# enclosure_controller_esp32.net
KiCad netlist of a schematic drawn in EAGLE
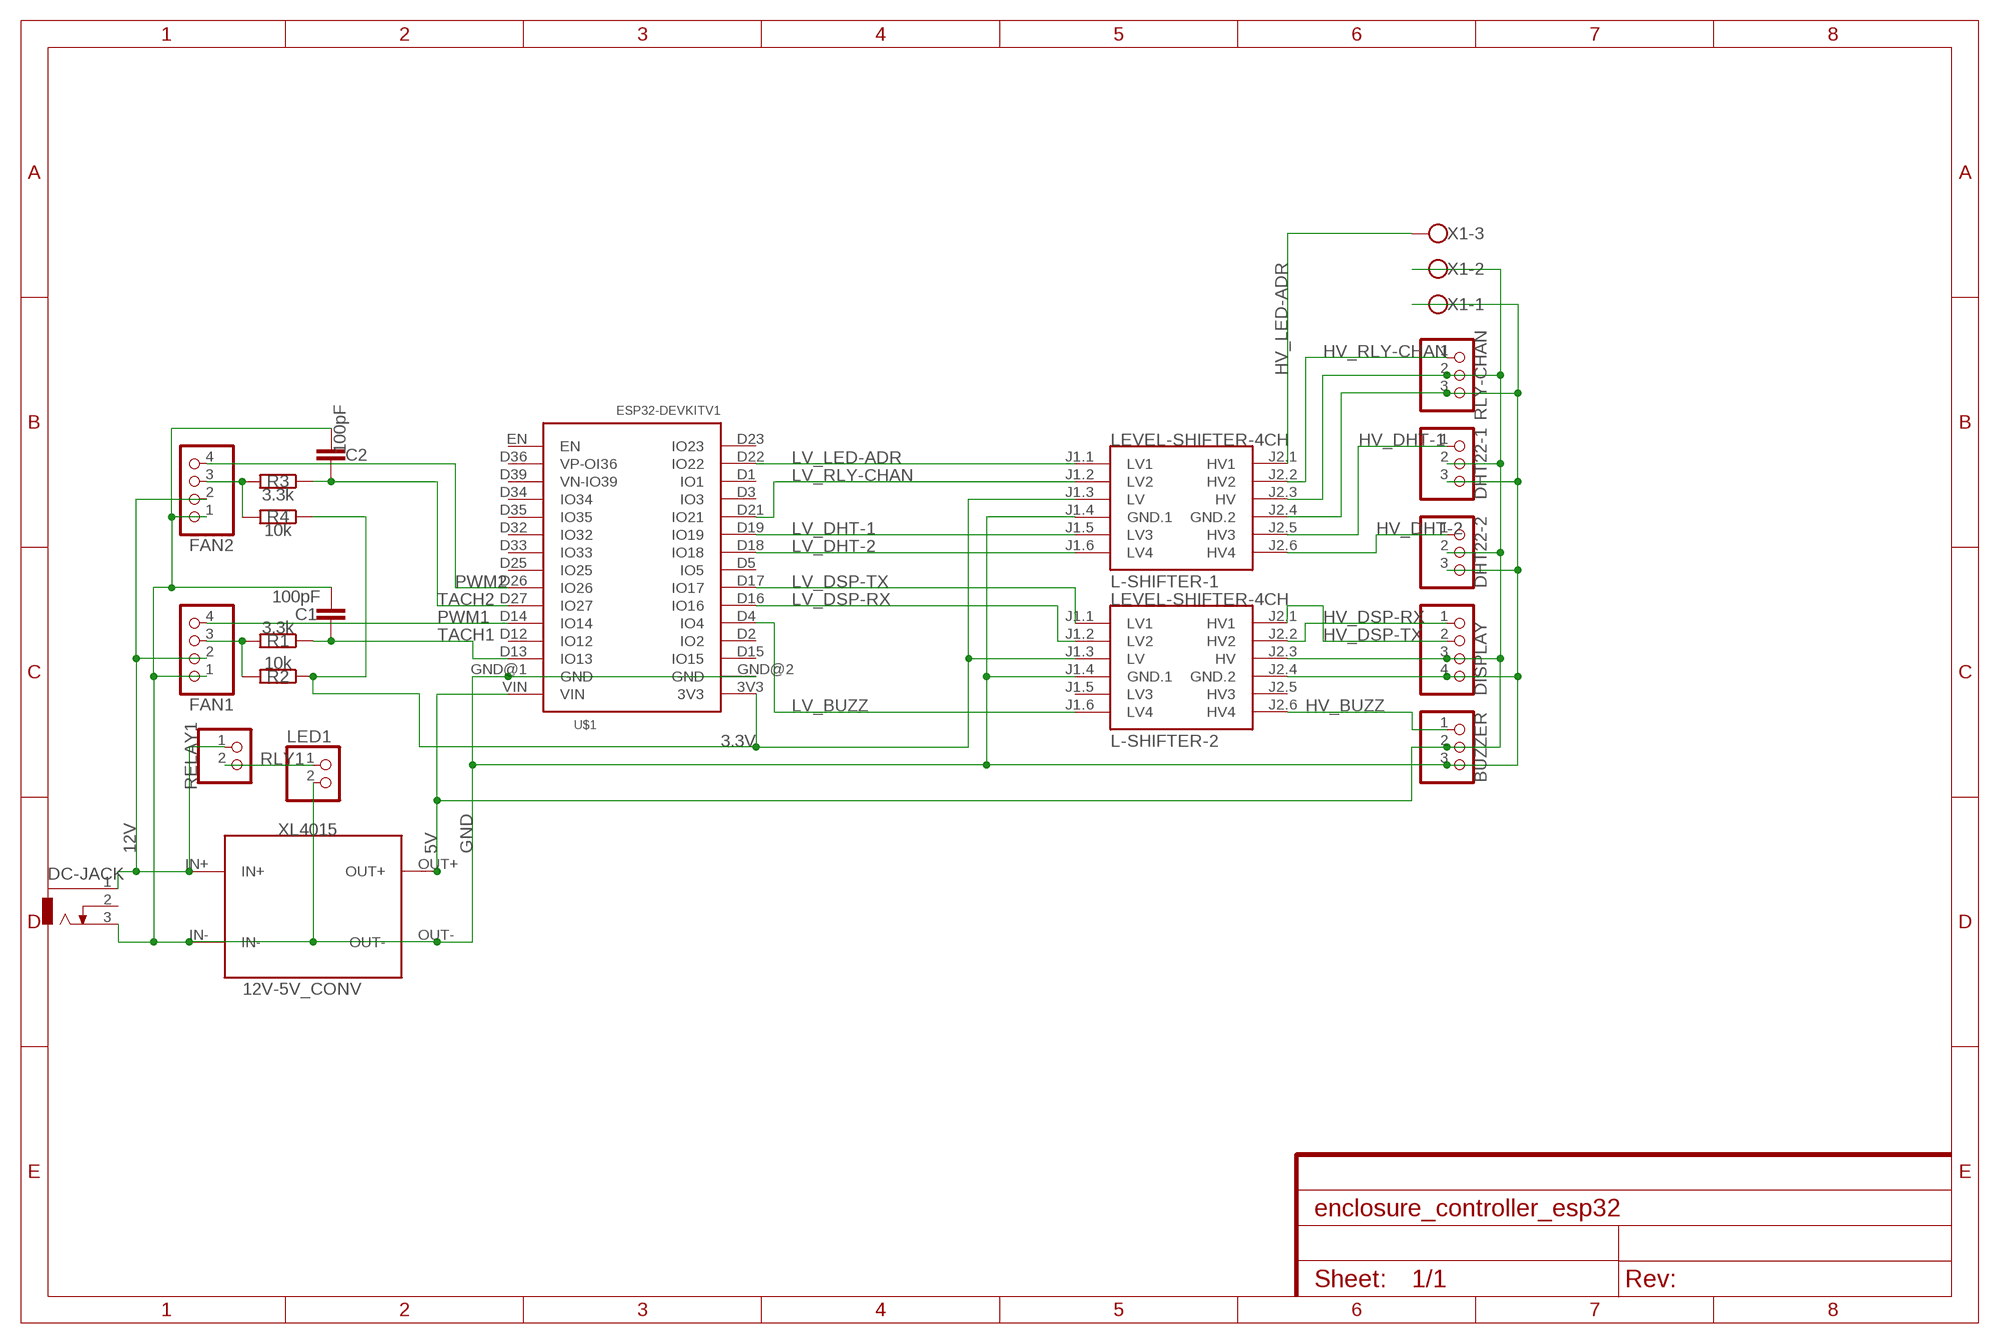
[diagram p0: schematic, sheet 1]

(export (version "E")
  (design (tool "Eeschema 10.0.6"))
  (components
    (comp (ref "12V-5V_CONV")
      (value "XL4015")
      (footprint "eagle-import:XL4015")
      (libsource (lib "eagle-import") (part "XL4015"))
    )
    (comp (ref "BUZZER")
      (value "PINHD-1X3")
      (footprint "eagle-import:1X03")
      (libsource (lib "eagle-import") (part "PINHD-1X3"))
    )
    (comp (ref "C1")
      (value "100pF")
      (footprint "eagle-import:C050-025X075")
      (libsource (lib "eagle-import") (part "C-EU050-025X075"))
    )
    (comp (ref "C2")
      (value "100pF")
      (footprint "eagle-import:C050-025X075")
      (libsource (lib "eagle-import") (part "C-EU050-025X075"))
    )
    (comp (ref "DC-JACK")
      (value "DCJ0303")
      (footprint "eagle-import:DCJ0303")
      (libsource (lib "eagle-import") (part "DCJ0303"))
    )
    (comp (ref "DHT22-1")
      (value "PINHD-1X3")
      (footprint "eagle-import:1X03")
      (libsource (lib "eagle-import") (part "PINHD-1X3"))
    )
    (comp (ref "DHT22-2")
      (value "PINHD-1X3")
      (footprint "eagle-import:1X03")
      (libsource (lib "eagle-import") (part "PINHD-1X3"))
    )
    (comp (ref "DISPLAY")
      (value "PINHD-1X4")
      (footprint "eagle-import:1X04")
      (libsource (lib "eagle-import") (part "PINHD-1X4"))
    )
    (comp (ref "FAN1")
      (value "PINHD-1X4")
      (footprint "eagle-import:1X04")
      (libsource (lib "eagle-import") (part "PINHD-1X4"))
    )
    (comp (ref "FAN2")
      (value "PINHD-1X4")
      (footprint "eagle-import:1X04")
      (libsource (lib "eagle-import") (part "PINHD-1X4"))
    )
    (comp (ref "L-SHIFTER-1")
      (value "LEVEL-SHIFTER-4CH")
      (footprint "eagle-import:LEVEL-SHIFTER-4CH")
      (libsource (lib "eagle-import") (part "LEVEL-SHIFTER-4CH"))
    )
    (comp (ref "L-SHIFTER-2")
      (value "LEVEL-SHIFTER-4CH")
      (footprint "eagle-import:LEVEL-SHIFTER-4CH")
      (libsource (lib "eagle-import") (part "LEVEL-SHIFTER-4CH"))
    )
    (comp (ref "LED1")
      (value "PINHD-1X2")
      (footprint "eagle-import:1X02")
      (libsource (lib "eagle-import") (part "PINHD-1X2"))
    )
    (comp (ref "R1")
      (value "3.3k")
      (footprint "eagle-import:0207_10")
      (libsource (lib "eagle-import") (part "R-EU_0207/10"))
    )
    (comp (ref "R2")
      (value "10k")
      (footprint "eagle-import:0207_10")
      (libsource (lib "eagle-import") (part "R-EU_0207/10"))
    )
    (comp (ref "R3")
      (value "3.3k")
      (footprint "eagle-import:0207_10")
      (libsource (lib "eagle-import") (part "R-EU_0207/10"))
    )
    (comp (ref "R4")
      (value "10k")
      (footprint "eagle-import:0207_10")
      (libsource (lib "eagle-import") (part "R-EU_0207/10"))
    )
    (comp (ref "RELAY1")
      (value "PINHD-1X2")
      (footprint "eagle-import:1X02")
      (libsource (lib "eagle-import") (part "PINHD-1X2"))
    )
    (comp (ref "RLY-CHAN")
      (value "PINHD-1X3")
      (footprint "eagle-import:1X03")
      (libsource (lib "eagle-import") (part "PINHD-1X3"))
    )
    (comp (ref "U$1")
      (value "ESP32DEVKITV1")
      (footprint "eagle-import:ESP32-DEVKITV1")
      (libsource (lib "eagle-import") (part "ESP32DEVKITV1"))
    )
    (comp (ref "X1")
      (value "LED2-ADR")
      (footprint "eagle-import:W237-103")
      (fields (field (name "MPN") "237-103"))
      (libsource (lib "eagle-import") (part "W237-103"))
    )
  )
  (nets
    (net (code "1") (name "/3.3V") (class "Default")
      (node (ref "L-SHIFTER-1") (pin "J1.3") (pinfunction "LV_J1.3") (pintype "power_in"))
      (node (ref "L-SHIFTER-2") (pin "J1.3") (pinfunction "LV_J1.3") (pintype "power_in"))
      (node (ref "R2") (pin "1") (pinfunction "1_1") (pintype "passive"))
      (node (ref "R4") (pin "1") (pinfunction "1_1") (pintype "passive"))
      (node (ref "U$1") (pin "3V3") (pinfunction "3V3_3V3") (pintype "bidirectional"))
    )
    (net (code "2") (name "/5V") (class "Default")
      (node (ref "12V-5V_CONV") (pin "OUT+") (pinfunction "OUT+_OUT+") (pintype "bidirectional"))
      (node (ref "BUZZER") (pin "2") (pinfunction "2_2") (pintype "passive"))
      (node (ref "DHT22-1") (pin "2") (pinfunction "2_2") (pintype "passive"))
      (node (ref "DHT22-2") (pin "2") (pinfunction "2_2") (pintype "passive"))
      (node (ref "DISPLAY") (pin "3") (pinfunction "3_3") (pintype "passive"))
      (node (ref "L-SHIFTER-1") (pin "J2.3") (pinfunction "HV_J2.3") (pintype "power_in"))
      (node (ref "L-SHIFTER-2") (pin "J2.3") (pinfunction "HV_J2.3") (pintype "power_in"))
      (node (ref "RLY-CHAN") (pin "2") (pinfunction "2_2") (pintype "passive"))
      (node (ref "U$1") (pin "VIN") (pinfunction "VIN_VIN") (pintype "bidirectional"))
      (node (ref "X1") (pin "2") (pinfunction "KL_2") (pintype "passive"))
    )
    (net (code "3") (name "/12V") (class "Default")
      (node (ref "12V-5V_CONV") (pin "IN+") (pinfunction "IN+_IN+") (pintype "bidirectional"))
      (node (ref "DC-JACK") (pin "1") (pinfunction "1_1") (pintype "passive"))
      (node (ref "FAN1") (pin "2") (pinfunction "2_2") (pintype "passive"))
      (node (ref "FAN2") (pin "2") (pinfunction "2_2") (pintype "passive"))
      (node (ref "RELAY1") (pin "1") (pinfunction "1_1") (pintype "passive"))
    )
    (net (code "4") (name "/GND") (class "Default")
      (node (ref "12V-5V_CONV") (pin "IN-") (pinfunction "IN-_IN-") (pintype "bidirectional"))
      (node (ref "12V-5V_CONV") (pin "OUT-") (pinfunction "OUT-_OUT-") (pintype "bidirectional"))
      (node (ref "BUZZER") (pin "3") (pinfunction "3_3") (pintype "passive"))
      (node (ref "C1") (pin "2") (pinfunction "2_2") (pintype "passive"))
      (node (ref "C2") (pin "1") (pinfunction "1_1") (pintype "passive"))
      (node (ref "DC-JACK") (pin "3") (pinfunction "3_3") (pintype "passive"))
      (node (ref "DHT22-1") (pin "3") (pinfunction "3_3") (pintype "passive"))
      (node (ref "DHT22-2") (pin "3") (pinfunction "3_3") (pintype "passive"))
      (node (ref "DISPLAY") (pin "4") (pinfunction "4_4") (pintype "passive"))
      (node (ref "FAN1") (pin "1") (pinfunction "1_1") (pintype "passive"))
      (node (ref "FAN2") (pin "1") (pinfunction "1_1") (pintype "passive"))
      (node (ref "L-SHIFTER-1") (pin "J1.4") (pinfunction "GND.1_J1.4") (pintype "power_in"))
      (node (ref "L-SHIFTER-1") (pin "J2.4") (pinfunction "GND.2_J2.4") (pintype "power_in"))
      (node (ref "L-SHIFTER-2") (pin "J1.4") (pinfunction "GND.1_J1.4") (pintype "power_in"))
      (node (ref "L-SHIFTER-2") (pin "J2.4") (pinfunction "GND.2_J2.4") (pintype "power_in"))
      (node (ref "LED1") (pin "2") (pinfunction "2_2") (pintype "passive"))
      (node (ref "RLY-CHAN") (pin "3") (pinfunction "3_3") (pintype "passive"))
      (node (ref "U$1") (pin "GND@1") (pinfunction "GND_GND@1") (pintype "bidirectional"))
      (node (ref "U$1") (pin "GND@2") (pinfunction "GND_GND@2") (pintype "bidirectional"))
      (node (ref "X1") (pin "1") (pinfunction "KL_1") (pintype "passive"))
    )
    (net (code "5") (name "/HV_BUZZ") (class "Default")
      (node (ref "BUZZER") (pin "1") (pinfunction "1_1") (pintype "passive"))
      (node (ref "L-SHIFTER-2") (pin "J2.6") (pinfunction "HV4_J2.6") (pintype "bidirectional"))
    )
    (net (code "6") (name "/HV_DHT-1") (class "Default")
      (node (ref "DHT22-1") (pin "1") (pinfunction "1_1") (pintype "passive"))
      (node (ref "L-SHIFTER-1") (pin "J2.5") (pinfunction "HV3_J2.5") (pintype "bidirectional"))
    )
    (net (code "7") (name "/HV_DHT-2") (class "Default")
      (node (ref "DHT22-2") (pin "1") (pinfunction "1_1") (pintype "passive"))
      (node (ref "L-SHIFTER-1") (pin "J2.6") (pinfunction "HV4_J2.6") (pintype "bidirectional"))
    )
    (net (code "8") (name "/HV_DSP-RX") (class "Default")
      (node (ref "DISPLAY") (pin "1") (pinfunction "1_1") (pintype "passive"))
      (node (ref "L-SHIFTER-2") (pin "J2.2") (pinfunction "HV2_J2.2") (pintype "bidirectional"))
    )
    (net (code "9") (name "/HV_DSP-TX") (class "Default")
      (node (ref "DISPLAY") (pin "2") (pinfunction "2_2") (pintype "passive"))
      (node (ref "L-SHIFTER-2") (pin "J2.1") (pinfunction "HV1_J2.1") (pintype "bidirectional"))
    )
    (net (code "10") (name "/HV_LED-ADR") (class "Default")
      (node (ref "L-SHIFTER-1") (pin "J2.1") (pinfunction "HV1_J2.1") (pintype "bidirectional"))
      (node (ref "X1") (pin "3") (pinfunction "KL_3") (pintype "passive"))
    )
    (net (code "11") (name "/HV_RLY-CHAN") (class "Default")
      (node (ref "L-SHIFTER-1") (pin "J2.2") (pinfunction "HV2_J2.2") (pintype "bidirectional"))
      (node (ref "RLY-CHAN") (pin "1") (pinfunction "1_1") (pintype "passive"))
    )
    (net (code "12") (name "/LV_BUZZ") (class "Default")
      (node (ref "L-SHIFTER-2") (pin "J1.6") (pinfunction "LV4_J1.6") (pintype "bidirectional"))
      (node (ref "U$1") (pin "D4") (pinfunction "IO4_D4") (pintype "bidirectional"))
    )
    (net (code "13") (name "/LV_DHT-1") (class "Default")
      (node (ref "L-SHIFTER-1") (pin "J1.5") (pinfunction "LV3_J1.5") (pintype "bidirectional"))
      (node (ref "U$1") (pin "D19") (pinfunction "IO19_D19") (pintype "bidirectional"))
    )
    (net (code "14") (name "/LV_DHT-2") (class "Default")
      (node (ref "L-SHIFTER-1") (pin "J1.6") (pinfunction "LV4_J1.6") (pintype "bidirectional"))
      (node (ref "U$1") (pin "D18") (pinfunction "IO18_D18") (pintype "bidirectional"))
    )
    (net (code "15") (name "/LV_DSP-RX") (class "Default")
      (node (ref "L-SHIFTER-2") (pin "J1.2") (pinfunction "LV2_J1.2") (pintype "bidirectional"))
      (node (ref "U$1") (pin "D16") (pinfunction "IO16_D16") (pintype "bidirectional"))
    )
    (net (code "16") (name "/LV_DSP-TX") (class "Default")
      (node (ref "L-SHIFTER-2") (pin "J1.1") (pinfunction "LV1_J1.1") (pintype "bidirectional"))
      (node (ref "U$1") (pin "D17") (pinfunction "IO17_D17") (pintype "bidirectional"))
    )
    (net (code "17") (name "/LV_LED-ADR") (class "Default")
      (node (ref "L-SHIFTER-1") (pin "J1.1") (pinfunction "LV1_J1.1") (pintype "bidirectional"))
      (node (ref "U$1") (pin "D22") (pinfunction "IO22_D22") (pintype "bidirectional"))
    )
    (net (code "18") (name "/LV_RLY-CHAN") (class "Default")
      (node (ref "L-SHIFTER-1") (pin "J1.2") (pinfunction "LV2_J1.2") (pintype "bidirectional"))
      (node (ref "U$1") (pin "D21") (pinfunction "IO21_D21") (pintype "bidirectional"))
    )
    (net (code "19") (name "/PWM1") (class "Default")
      (node (ref "FAN1") (pin "4") (pinfunction "4_4") (pintype "passive"))
      (node (ref "U$1") (pin "D14") (pinfunction "IO14_D14") (pintype "bidirectional"))
    )
    (net (code "20") (name "/PWM2") (class "Default")
      (node (ref "FAN2") (pin "4") (pinfunction "4_4") (pintype "passive"))
      (node (ref "U$1") (pin "D26") (pinfunction "IO26_D26") (pintype "bidirectional"))
    )
    (net (code "21") (name "/RLY1") (class "Default")
      (node (ref "LED1") (pin "1") (pinfunction "1_1") (pintype "passive"))
      (node (ref "RELAY1") (pin "2") (pinfunction "2_2") (pintype "passive"))
    )
    (net (code "22") (name "/TACH1") (class "Default")
      (node (ref "C1") (pin "1") (pinfunction "1_1") (pintype "passive"))
      (node (ref "FAN1") (pin "3") (pinfunction "3_3") (pintype "passive"))
      (node (ref "R1") (pin "1") (pinfunction "1_1") (pintype "passive"))
      (node (ref "R1") (pin "2") (pinfunction "2_2") (pintype "passive"))
      (node (ref "R2") (pin "2") (pinfunction "2_2") (pintype "passive"))
      (node (ref "U$1") (pin "D13") (pinfunction "IO13_D13") (pintype "bidirectional"))
    )
    (net (code "23") (name "/TACH2") (class "Default")
      (node (ref "C2") (pin "2") (pinfunction "2_2") (pintype "passive"))
      (node (ref "FAN2") (pin "3") (pinfunction "3_3") (pintype "passive"))
      (node (ref "R3") (pin "1") (pinfunction "1_1") (pintype "passive"))
      (node (ref "R3") (pin "2") (pinfunction "2_2") (pintype "passive"))
      (node (ref "R4") (pin "2") (pinfunction "2_2") (pintype "passive"))
      (node (ref "U$1") (pin "D27") (pinfunction "IO27_D27") (pintype "bidirectional"))
    )
    (net (code "24") (name "unconnected-(DC-JACK-Pad2)") (class "Default")
      (node (ref "DC-JACK") (pin "2") (pinfunction "2_2") (pintype "passive"))
    )
    (net (code "25") (name "unconnected-(L-SHIFTER-2-HV3-PadJ2.5)") (class "Default")
      (node (ref "L-SHIFTER-2") (pin "J2.5") (pinfunction "HV3_J2.5") (pintype "bidirectional"))
    )
    (net (code "26") (name "unconnected-(L-SHIFTER-2-LV3-PadJ1.5)") (class "Default")
      (node (ref "L-SHIFTER-2") (pin "J1.5") (pinfunction "LV3_J1.5") (pintype "bidirectional"))
    )
    (net (code "27") (name "unconnected-(U$1-IO1-PadD1)") (class "Default")
      (node (ref "U$1") (pin "D1") (pinfunction "IO1_D1") (pintype "bidirectional"))
    )
    (net (code "28") (name "unconnected-(U$1-IO2-PadD2)") (class "Default")
      (node (ref "U$1") (pin "D2") (pinfunction "IO2_D2") (pintype "bidirectional"))
    )
    (net (code "29") (name "unconnected-(U$1-IO3-PadD3)") (class "Default")
      (node (ref "U$1") (pin "D3") (pinfunction "IO3_D3") (pintype "bidirectional"))
    )
    (net (code "30") (name "unconnected-(U$1-IO5-PadD5)") (class "Default")
      (node (ref "U$1") (pin "D5") (pinfunction "IO5_D5") (pintype "bidirectional"))
    )
    (net (code "31") (name "unconnected-(U$1-IO12-PadD12)") (class "Default")
      (node (ref "U$1") (pin "D12") (pinfunction "IO12_D12") (pintype "bidirectional"))
    )
    (net (code "32") (name "unconnected-(U$1-IO15-PadD15)") (class "Default")
      (node (ref "U$1") (pin "D15") (pinfunction "IO15_D15") (pintype "bidirectional"))
    )
    (net (code "33") (name "unconnected-(U$1-IO23-PadD23)") (class "Default")
      (node (ref "U$1") (pin "D23") (pinfunction "IO23_D23") (pintype "bidirectional"))
    )
    (net (code "34") (name "unconnected-(U$1-IO25-PadD25)") (class "Default")
      (node (ref "U$1") (pin "D25") (pinfunction "IO25_D25") (pintype "bidirectional"))
    )
    (net (code "35") (name "unconnected-(U$1-IO32-PadD32)") (class "Default")
      (node (ref "U$1") (pin "D32") (pinfunction "IO32_D32") (pintype "bidirectional"))
    )
    (net (code "36") (name "unconnected-(U$1-IO33-PadD33)") (class "Default")
      (node (ref "U$1") (pin "D33") (pinfunction "IO33_D33") (pintype "bidirectional"))
    )
    (net (code "37") (name "unconnected-(U$1-IO34-PadD34)") (class "Default")
      (node (ref "U$1") (pin "D34") (pinfunction "IO34_D34") (pintype "bidirectional"))
    )
    (net (code "38") (name "unconnected-(U$1-IO35-PadD35)") (class "Default")
      (node (ref "U$1") (pin "D35") (pinfunction "IO35_D35") (pintype "bidirectional"))
    )
    (net (code "39") (name "unconnected-(U$1-PadEN)") (class "Default")
      (node (ref "U$1") (pin "EN") (pinfunction "EN_EN") (pintype "bidirectional"))
    )
    (net (code "40") (name "unconnected-(U$1-VN-IO39-PadD39)") (class "Default")
      (node (ref "U$1") (pin "D39") (pinfunction "VN-IO39_D39") (pintype "bidirectional"))
    )
    (net (code "41") (name "unconnected-(U$1-VP-OI36-PadD36)") (class "Default")
      (node (ref "U$1") (pin "D36") (pinfunction "VP-OI36_D36") (pintype "bidirectional"))
    )
  )
)
